# Frontend.net
KiCad netlist of a schematic drawn in Altium Designer
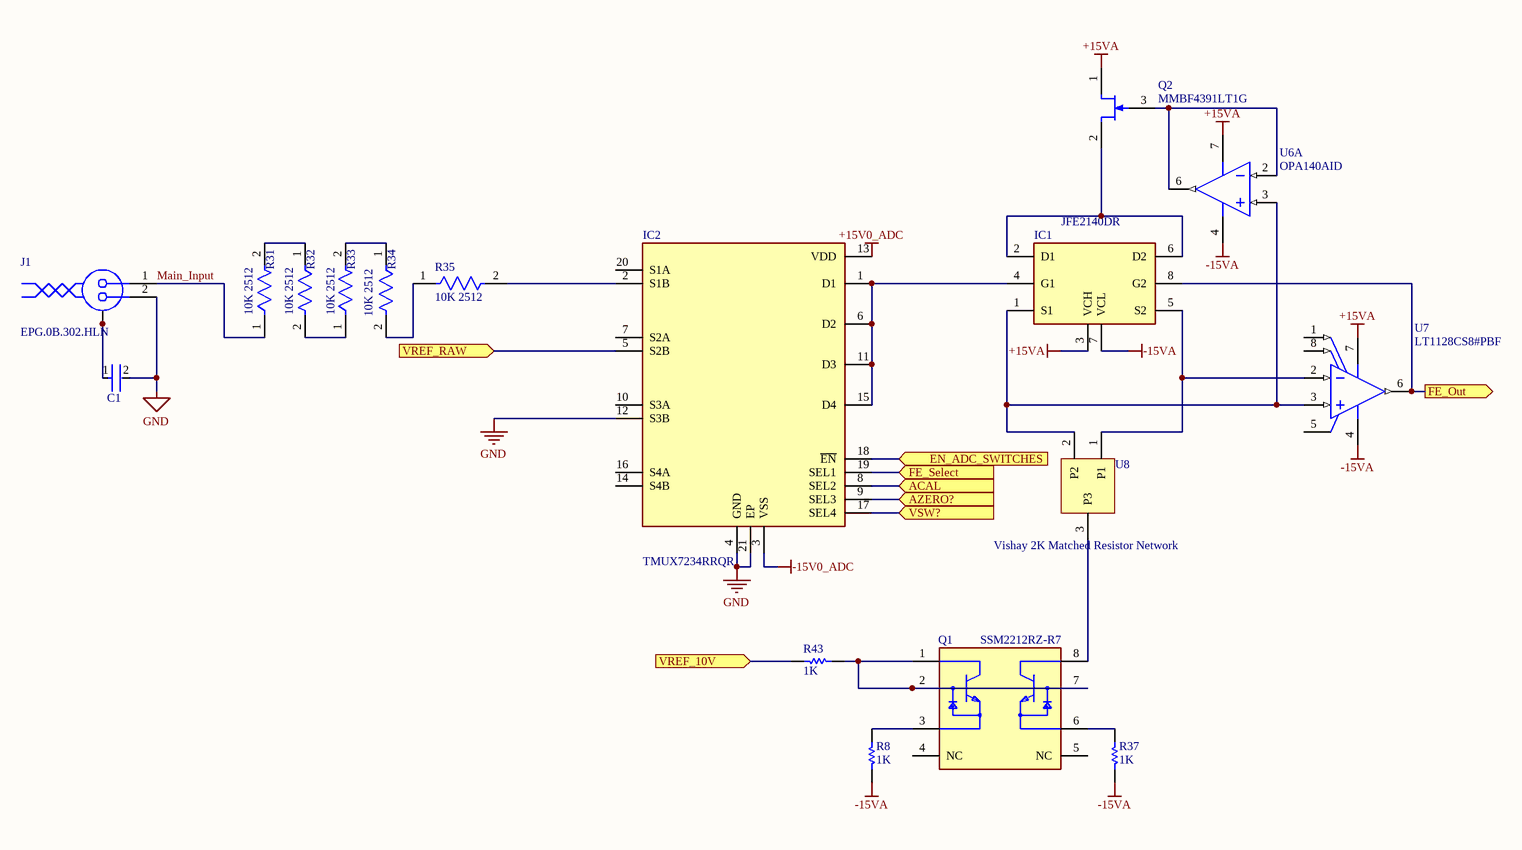
[diagram p0: Frontend.SchDoc]

(export (version "E")
  (design (tool "Eeschema 10.0.6"))
  (components
    (comp (ref "C1")
      (value "CGA3E2X7R1H104K080AA")
      (footprint "FP-CGA3E-0_3-0_1-IPC_A")
      (description "Cap Ceramic 100nF 50V X7R 10% Pad SMD 0603 +125°C Automotive T/R")
      (fields (field (name "TOLERANCE") "10%") (field (name "VOLTAGE") "50V"))
      (libsource (lib "Altium Content Vault") (part "b4654b650e69147ec39a6b967a45e02"))
    )
    (comp (ref "IC1")
      (value "JFE2140DR")
      (footprint "SOIC127P600X175-8N")
      (description "Integrated Circuit")
      (fields (field (name "MOUSER PART NUMBER") "595-JFE2140DR"))
      (libsource (lib "SamacSys") (part "JFE2140DR"))
    )
    (comp (ref "IC2")
      (value "TMUX7234RRQR")
      (footprint "QFN50P400X400X80-21N-D")
      (description "Integrated Circuit")
      (fields (field (name "MOUSER PART NUMBER") "595-TMUX7234RRQR"))
      (libsource (lib "SamacSys") (part "TMUX7234RRQR"))
    )
    (comp (ref "J1")
      (value "EPG.0B.302.HLN")
      (footprint "EPG.0B.302.HLN")
      (fields (field (name "MANUFACTURER") "LEMO"))
      (libsource (lib "Altium Content Vault") (part "LEMO-CN-RP-R2_1"))
    )
    (comp (ref "Q1")
      (value "SSM2212RZ-R7")
      (footprint "FP-R-8-IPC_C")
      (description "TRANS 2NPN 40V 0.02A 8SOIC")
      (libsource (lib "Altium Content Vault") (part "dca280efab45baf6817a88e10cd7010"))
    )
    (comp (ref "Q2")
      (value "MMBF4391LT1G")
      (footprint "ONSC-SOT-23-3-318-08_V")
      (description "JFET Switching Transistor, N-Channel, 3-Pin SOT-23, Pb-Free, Tape and Reel")
      (fields (field (name "MANUFACTURER") "On Semiconductor"))
      (libsource (lib "Altium Content Vault") (part "ONSC-JFET-D1S2G3-3-B"))
    )
    (comp (ref "R8")
      (value "1K")
      (footprint "RESC2013X60X35ML10T20")
      (description "Chip Resistor, 1 KOhm, +/- 1%, 125 mW, -55 to 155 degC, 0805 (2012 Metric), RoHS, Tape and Reel")
      (fields (field (name "TOLERANCE") "1%") (field (name "MANUFACTURER") "Yageo"))
      (libsource (lib "Altium Content Vault") (part "RES-2"))
    )
    (comp (ref "R31")
      (value "10K 2512")
      (footprint "FP-CRCW2512-e3-MFG")
      (description "RES Thick Film, 100kΩ, 1%, 1W, 100ppm/°C, 2512")
      (fields (field (name "TOLERANCE") "1%"))
      (libsource (lib "Altium Content Vault") (part "1029c3af85768c4190bb7ad29bc67b5"))
    )
    (comp (ref "R32")
      (value "10K 2512")
      (footprint "FP-CRCW2512-e3-MFG")
      (description "RES Thick Film, 100kΩ, 1%, 1W, 100ppm/°C, 2512")
      (fields (field (name "TOLERANCE") "1%"))
      (libsource (lib "Altium Content Vault") (part "1029c3af85768c4190bb7ad29bc67b5"))
    )
    (comp (ref "R33")
      (value "10K 2512")
      (footprint "FP-CRCW2512-e3-MFG")
      (description "RES Thick Film, 100kΩ, 1%, 1W, 100ppm/°C, 2512")
      (fields (field (name "TOLERANCE") "1%"))
      (libsource (lib "Altium Content Vault") (part "1029c3af85768c4190bb7ad29bc67b5"))
    )
    (comp (ref "R34")
      (value "10K 2512")
      (footprint "FP-CRCW2512-e3-MFG")
      (description "RES Thick Film, 100kΩ, 1%, 1W, 100ppm/°C, 2512")
      (fields (field (name "TOLERANCE") "1%"))
      (libsource (lib "Altium Content Vault") (part "1029c3af85768c4190bb7ad29bc67b5"))
    )
    (comp (ref "R35")
      (value "10K 2512")
      (footprint "FP-CRCW2512-e3-MFG")
      (description "RES Thick Film, 100kΩ, 1%, 1W, 100ppm/°C, 2512")
      (fields (field (name "TOLERANCE") "1%"))
      (libsource (lib "Altium Content Vault") (part "1029c3af85768c4190bb7ad29bc67b5"))
    )
    (comp (ref "R37")
      (value "1K")
      (footprint "RESC2013X60X35ML10T20")
      (description "Chip Resistor, 1 KOhm, +/- 1%, 125 mW, -55 to 155 degC, 0805 (2012 Metric), RoHS, Tape and Reel")
      (fields (field (name "TOLERANCE") "1%") (field (name "MANUFACTURER") "Yageo"))
      (libsource (lib "Altium Content Vault") (part "RES-2"))
    )
    (comp (ref "R43")
      (value "1K")
      (footprint "RESC2013X60X35ML10T20")
      (description "Chip Resistor, 1 KOhm, +/- 1%, 125 mW, -55 to 155 degC, 0805 (2012 Metric), RoHS, Tape and Reel")
      (fields (field (name "TOLERANCE") "1%") (field (name "MANUFACTURER") "Yageo"))
      (libsource (lib "Altium Content Vault") (part "RES-2"))
    )
    (comp (ref "U6")
      (value "OPA140AID")
      (footprint "D0008A_M")
      (fields (field (name "MANUFACTURER") "Texas Instruments"))
      (libsource (lib "Altium Content Vault") (part "TI-OPA-8_1"))
    )
    (comp (ref "U7")
      (value "LT1128CS8#PBF")
      (footprint "LT-S8-8_M")
      (fields
        (field (name "LINEAR TECHNOLOGY PART NUMBER") "LT1128")
        (field (name "MANUFACTURER") "Linear Technology")
      )
      (libsource (lib "Altium Content Vault") (part "LT-LT1128-S8-8"))
    )
    (comp (ref "U8")
      (value "Vishay 2K Matched Resistor Network")
      (footprint "MAXM-U3+2_L")
      (fields (field (name "PARTNUMBER") "MAX5491LC01000+T"))
      (libsource (lib "Altium Content Vault") (part "MAX549X-U3X2"))
    )
  )
  (nets
    (net (code "1") (name "+15V0_ADC") (class "Default")
      (node (ref "IC2") (pin "13") (pinfunction "VDD_13") (pintype "passive"))
    )
    (net (code "2") (name "+15VA") (class "Default")
      (node (ref "IC1") (pin "3") (pinfunction "VCH_3") (pintype "passive"))
      (node (ref "Q2") (pin "1") (pinfunction "D_1") (pintype "passive"))
      (node (ref "U6") (pin "7") (pinfunction "V+_7") (pintype "power_in"))
      (node (ref "U7") (pin "7") (pinfunction "V+_7") (pintype "power_in"))
    )
    (net (code "3") (name "-15V0_ADC") (class "Default")
      (node (ref "IC2") (pin "3") (pinfunction "VSS_3") (pintype "passive"))
    )
    (net (code "4") (name "-15VA") (class "Default")
      (node (ref "IC1") (pin "7") (pinfunction "VCL_7") (pintype "passive"))
      (node (ref "R37") (pin "1") (pinfunction "1_1") (pintype "passive"))
      (node (ref "R8") (pin "1") (pinfunction "1_1") (pintype "passive"))
      (node (ref "U6") (pin "4") (pinfunction "V-_4") (pintype "power_in"))
      (node (ref "U7") (pin "4") (pinfunction "V-_4") (pintype "power_in"))
    )
    (net (code "5") (name "/ACAL") (class "Default")
      (node (ref "IC2") (pin "8") (pinfunction "SEL2_8") (pintype "passive"))
    )
    (net (code "6") (name "/AZERO?") (class "Default")
      (node (ref "IC2") (pin "9") (pinfunction "SEL3_9") (pintype "passive"))
    )
    (net (code "7") (name "/EN_ADC_SWITCHES") (class "Default")
      (node (ref "IC2") (pin "18") (pinfunction "~{EN}_18") (pintype "passive"))
    )
    (net (code "8") (name "/FE_Out") (class "Default")
      (node (ref "IC1") (pin "8") (pinfunction "G2_8") (pintype "passive"))
      (node (ref "U7") (pin "6") (pinfunction "OUT_6") (pintype "output"))
    )
    (net (code "9") (name "/FE_Select") (class "Default")
      (node (ref "IC2") (pin "19") (pinfunction "SEL1_19") (pintype "passive"))
    )
    (net (code "10") (name "/Main_Input") (class "Default")
      (node (ref "J1") (pin "1") (pinfunction "1_1") (pintype "passive"))
      (node (ref "R31") (pin "1") (pinfunction "1_1") (pintype "passive"))
    )
    (net (code "11") (name "/VREF_10V") (class "Default")
      (node (ref "R43") (pin "1") (pinfunction "1_1") (pintype "passive"))
    )
    (net (code "12") (name "/VREF_RAW") (class "Default")
      (node (ref "IC2") (pin "5") (pinfunction "S2B_5") (pintype "passive"))
    )
    (net (code "13") (name "/VSW?") (class "Default")
      (node (ref "IC2") (pin "17") (pinfunction "SEL4_17") (pintype "passive"))
    )
    (net (code "14") (name "GND") (class "Default")
      (node (ref "C1") (pin "2") (pinfunction "2_2") (pintype "passive"))
      (node (ref "IC2") (pin "12") (pinfunction "S3B_12") (pintype "passive"))
      (node (ref "IC2") (pin "21") (pinfunction "EP_21") (pintype "passive"))
      (node (ref "IC2") (pin "4") (pinfunction "GND_4") (pintype "passive"))
      (node (ref "J1") (pin "2") (pinfunction "2_2") (pintype "passive"))
    )
    (net (code "15") (name "Net-(C1-Pad1)") (class "Default")
      (node (ref "C1") (pin "1") (pinfunction "1_1") (pintype "passive"))
      (node (ref "J1") (pin "4") (pinfunction "4_4") (pintype "passive"))
      (node (ref "J1") (pin "5") (pinfunction "5_5") (pintype "passive"))
      (node (ref "J1") (pin "6") (pinfunction "6_6") (pintype "passive"))
      (node (ref "J1") (pin "7") (pinfunction "7_7") (pintype "passive"))
    )
    (net (code "16") (name "Net-(IC1-D1)") (class "Default")
      (node (ref "IC1") (pin "2") (pinfunction "D1_2") (pintype "passive"))
      (node (ref "IC1") (pin "6") (pinfunction "D2_6") (pintype "passive"))
      (node (ref "Q2") (pin "2") (pinfunction "S_2") (pintype "passive"))
    )
    (net (code "17") (name "Net-(IC1-G1)") (class "Default")
      (node (ref "IC1") (pin "4") (pinfunction "G1_4") (pintype "passive"))
      (node (ref "IC2") (pin "1") (pinfunction "D1_1") (pintype "passive"))
      (node (ref "IC2") (pin "11") (pinfunction "D3_11") (pintype "passive"))
      (node (ref "IC2") (pin "15") (pinfunction "D4_15") (pintype "passive"))
      (node (ref "IC2") (pin "6") (pinfunction "D2_6") (pintype "passive"))
    )
    (net (code "18") (name "Net-(IC1-S1)") (class "Default")
      (node (ref "IC1") (pin "1") (pinfunction "S1_1") (pintype "passive"))
      (node (ref "U6") (pin "3") (pinfunction "IN+_3") (pintype "input"))
      (node (ref "U7") (pin "3") (pinfunction "+IN_3") (pintype "input"))
      (node (ref "U8") (pin "2") (pinfunction "P2_2") (pintype "passive"))
    )
    (net (code "19") (name "Net-(IC1-S2)") (class "Default")
      (node (ref "IC1") (pin "5") (pinfunction "S2_5") (pintype "passive"))
      (node (ref "U7") (pin "2") (pinfunction "-IN_2") (pintype "input"))
      (node (ref "U8") (pin "1") (pinfunction "P1_1") (pintype "passive"))
    )
    (net (code "20") (name "Net-(IC2-S1B)") (class "Default")
      (node (ref "IC2") (pin "2") (pinfunction "S1B_2") (pintype "passive"))
      (node (ref "R35") (pin "2") (pinfunction "2_2") (pintype "passive"))
    )
    (net (code "21") (name "Net-(Q1-B1)") (class "Default")
      (node (ref "Q1") (pin "1") (pinfunction "C1_1") (pintype "passive"))
      (node (ref "Q1") (pin "2") (pinfunction "B1_2") (pintype "passive"))
      (node (ref "Q1") (pin "7") (pinfunction "B2_7") (pintype "passive"))
      (node (ref "R43") (pin "2") (pinfunction "2_2") (pintype "passive"))
    )
    (net (code "22") (name "Net-(Q1-C2)") (class "Default")
      (node (ref "Q1") (pin "8") (pinfunction "C2_8") (pintype "passive"))
      (node (ref "U8") (pin "3") (pinfunction "P3_3") (pintype "passive"))
    )
    (net (code "23") (name "Net-(Q1-E1)") (class "Default")
      (node (ref "Q1") (pin "3") (pinfunction "E1_3") (pintype "passive"))
      (node (ref "R8") (pin "2") (pinfunction "2_2") (pintype "passive"))
    )
    (net (code "24") (name "Net-(Q1-E2)") (class "Default")
      (node (ref "Q1") (pin "6") (pinfunction "E2_6") (pintype "passive"))
      (node (ref "R37") (pin "2") (pinfunction "2_2") (pintype "passive"))
    )
    (net (code "25") (name "Net-(Q2-G)") (class "Default")
      (node (ref "Q2") (pin "3") (pinfunction "G_3") (pintype "passive"))
      (node (ref "U6") (pin "2") (pinfunction "IN-_2") (pintype "input"))
      (node (ref "U6") (pin "6") (pinfunction "OUT_6") (pintype "output"))
    )
    (net (code "26") (name "Net-(R31-Pad2)") (class "Default")
      (node (ref "R31") (pin "2") (pinfunction "2_2") (pintype "passive"))
      (node (ref "R32") (pin "1") (pinfunction "1_1") (pintype "passive"))
    )
    (net (code "27") (name "Net-(R32-Pad2)") (class "Default")
      (node (ref "R32") (pin "2") (pinfunction "2_2") (pintype "passive"))
      (node (ref "R33") (pin "1") (pinfunction "1_1") (pintype "passive"))
    )
    (net (code "28") (name "Net-(R33-Pad2)") (class "Default")
      (node (ref "R33") (pin "2") (pinfunction "2_2") (pintype "passive"))
      (node (ref "R34") (pin "1") (pinfunction "1_1") (pintype "passive"))
    )
    (net (code "29") (name "Net-(R34-Pad2)") (class "Default")
      (node (ref "R34") (pin "2") (pinfunction "2_2") (pintype "passive"))
      (node (ref "R35") (pin "1") (pinfunction "1_1") (pintype "passive"))
    )
    (net (code "30") (name "unconnected-(IC2-S1A-Pad20)") (class "Default")
      (node (ref "IC2") (pin "20") (pinfunction "S1A_20") (pintype "passive"))
    )
    (net (code "31") (name "unconnected-(IC2-S2A-Pad7)") (class "Default")
      (node (ref "IC2") (pin "7") (pinfunction "S2A_7") (pintype "passive"))
    )
    (net (code "32") (name "unconnected-(IC2-S3A-Pad10)") (class "Default")
      (node (ref "IC2") (pin "10") (pinfunction "S3A_10") (pintype "passive"))
    )
    (net (code "33") (name "unconnected-(IC2-S4A-Pad16)") (class "Default")
      (node (ref "IC2") (pin "16") (pinfunction "S4A_16") (pintype "passive"))
    )
    (net (code "34") (name "unconnected-(IC2-S4B-Pad14)") (class "Default")
      (node (ref "IC2") (pin "14") (pinfunction "S4B_14") (pintype "passive"))
    )
    (net (code "35") (name "unconnected-(Q1-NC-Pad4)") (class "Default")
      (node (ref "Q1") (pin "4") (pinfunction "NC_4") (pintype "passive"))
    )
    (net (code "36") (name "unconnected-(Q1-NC-Pad5)") (class "Default")
      (node (ref "Q1") (pin "5") (pinfunction "NC_5") (pintype "passive"))
    )
    (net (code "37") (name "unconnected-(U7-OVERCOMP-Pad5)") (class "Default")
      (node (ref "U7") (pin "5") (pinfunction "OVERCOMP_5") (pintype "passive"))
    )
    (net (code "38") (name "unconnected-(U7-VOS_TRIM-Pad1)") (class "Default")
      (node (ref "U7") (pin "1") (pinfunction "VOS_TRIM_1") (pintype "input"))
    )
    (net (code "39") (name "unconnected-(U7-VOS_TRIM-Pad8)") (class "Default")
      (node (ref "U7") (pin "8") (pinfunction "VOS_TRIM_8") (pintype "input"))
    )
  )
)
